# 85-2031red.net
KiCad netlist of a schematic drawn in EAGLE
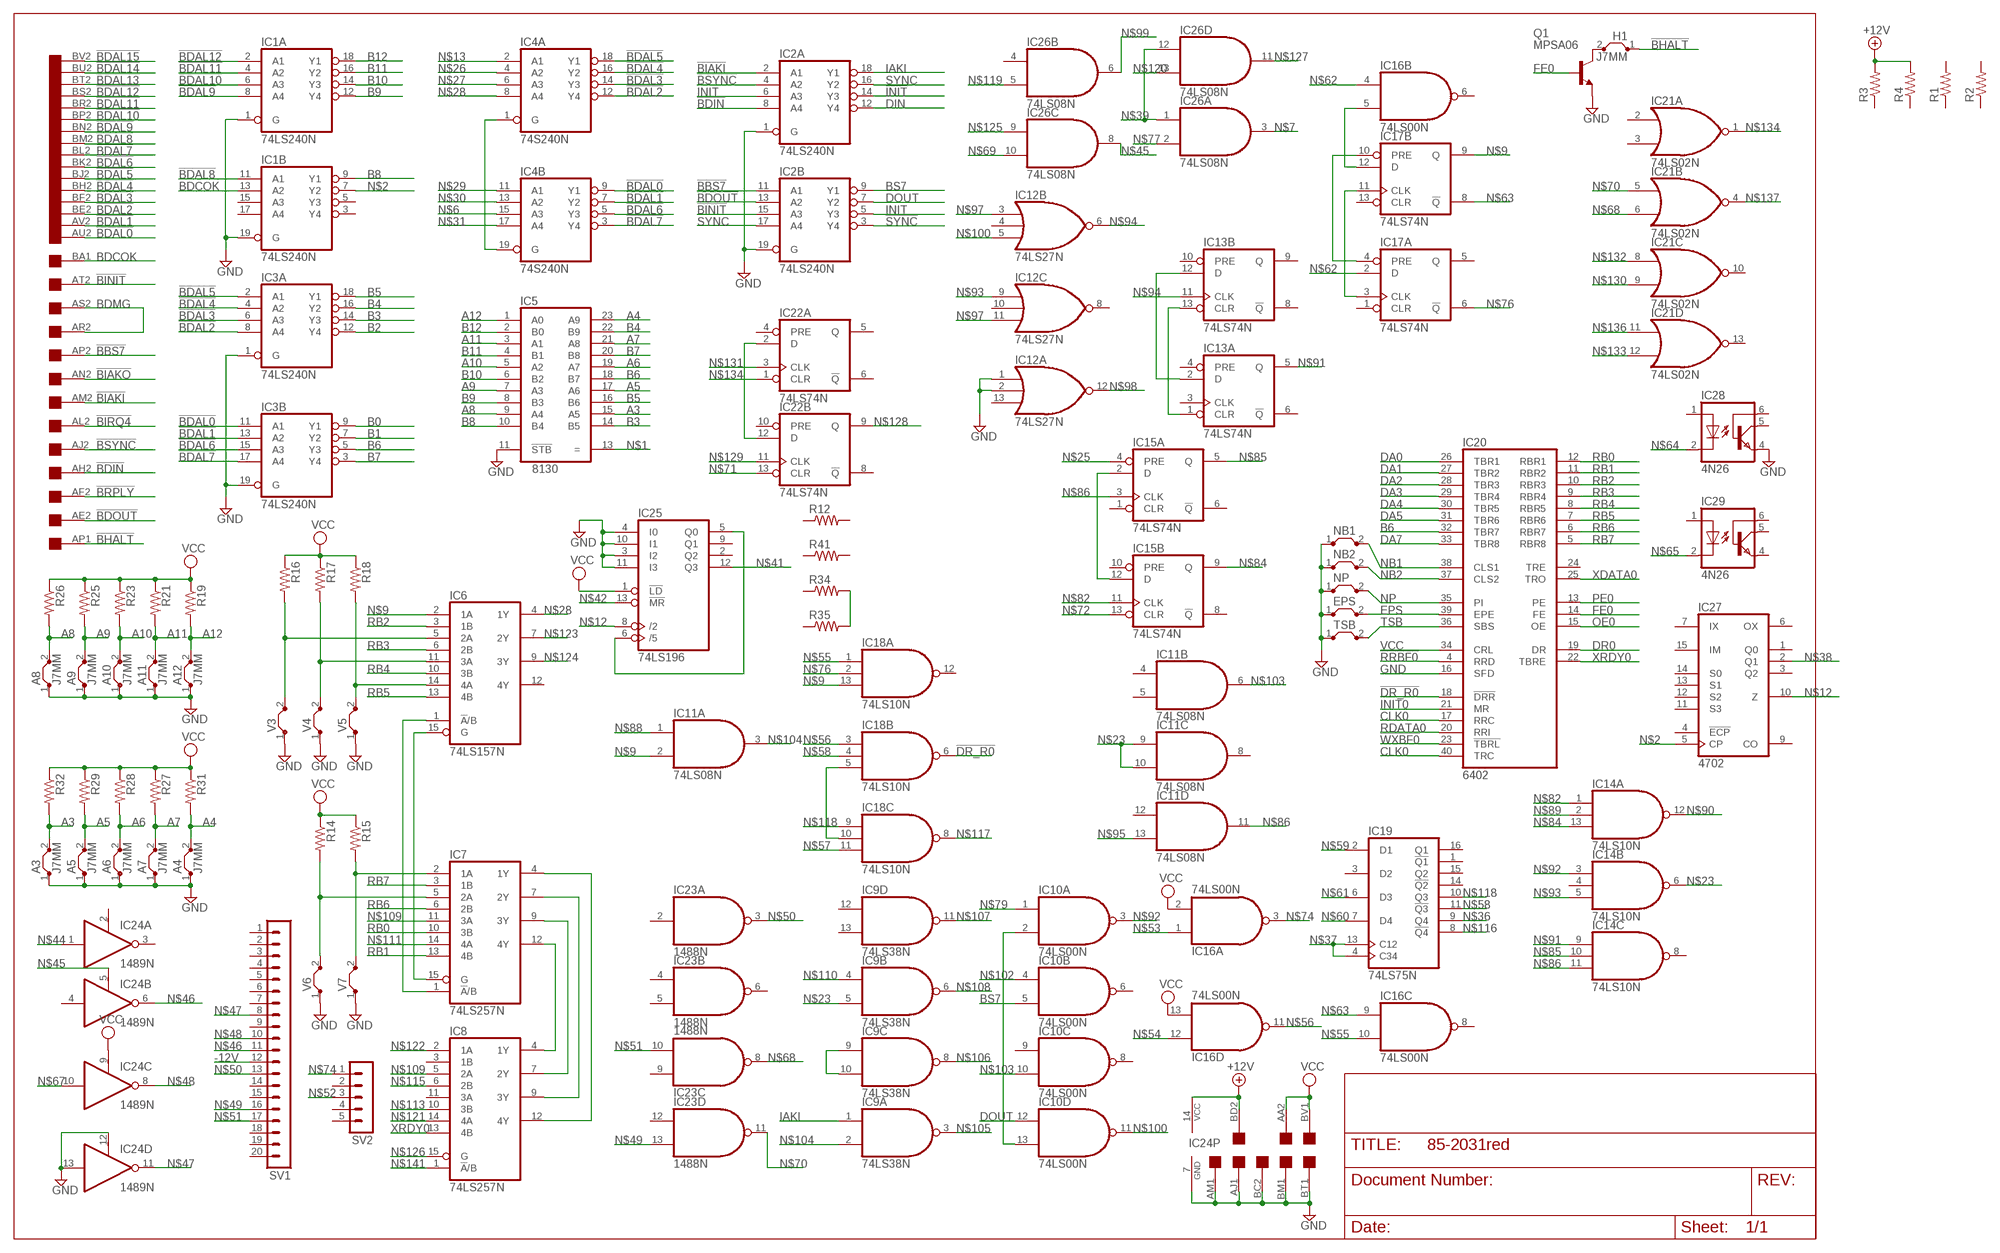
[diagram p0: schematic, sheet 1]

(export (version "E")
  (design (tool "Eeschema 10.0.6"))
  (components
    (comp (ref "A3")
      (value "J7MM")
      (footprint "eagle-import:07")
      (libsource (lib "eagle-import") (part "J7MM"))
    )
    (comp (ref "A4")
      (value "J7MM")
      (footprint "eagle-import:07")
      (libsource (lib "eagle-import") (part "J7MM"))
    )
    (comp (ref "A5")
      (value "J7MM")
      (footprint "eagle-import:07")
      (libsource (lib "eagle-import") (part "J7MM"))
    )
    (comp (ref "A6")
      (value "J7MM")
      (footprint "eagle-import:07")
      (libsource (lib "eagle-import") (part "J7MM"))
    )
    (comp (ref "A7")
      (value "J7MM")
      (footprint "eagle-import:07")
      (libsource (lib "eagle-import") (part "J7MM"))
    )
    (comp (ref "A8")
      (value "J7MM")
      (footprint "eagle-import:07")
      (libsource (lib "eagle-import") (part "J7MM"))
    )
    (comp (ref "A9")
      (value "J7MM")
      (footprint "eagle-import:07")
      (libsource (lib "eagle-import") (part "J7MM"))
    )
    (comp (ref "A10")
      (value "J7MM")
      (footprint "eagle-import:07")
      (libsource (lib "eagle-import") (part "J7MM"))
    )
    (comp (ref "A11")
      (value "J7MM")
      (footprint "eagle-import:07")
      (libsource (lib "eagle-import") (part "J7MM"))
    )
    (comp (ref "A12")
      (value "J7MM")
      (footprint "eagle-import:07")
      (libsource (lib "eagle-import") (part "J7MM"))
    )
    (comp (ref "EDGE$")
      (value "DOUBLE")
      (footprint "eagle-import:EDGE-CON4")
      (libsource (lib "eagle-import") (part "DOUBLE"))
    )
    (comp (ref "EPS")
      (value "J7MM")
      (footprint "eagle-import:07")
      (libsource (lib "eagle-import") (part "J7MM"))
    )
    (comp (ref "H1")
      (value "J7MM")
      (footprint "eagle-import:07")
      (libsource (lib "eagle-import") (part "J7MM"))
    )
    (comp (ref "IC1")
      (value "74LS240N")
      (footprint "eagle-import:DIL20")
      (libsource (lib "eagle-import") (part "74240NLS"))
    )
    (comp (ref "IC2")
      (value "74LS240N")
      (footprint "eagle-import:DIL20")
      (libsource (lib "eagle-import") (part "74240NLS"))
    )
    (comp (ref "IC3")
      (value "74LS240N")
      (footprint "eagle-import:DIL20")
      (libsource (lib "eagle-import") (part "74240NLS"))
    )
    (comp (ref "IC4")
      (value "74S240N")
      (footprint "eagle-import:DIL20")
      (libsource (lib "eagle-import") (part "74240NS"))
    )
    (comp (ref "IC5")
      (value "8130")
      (footprint "eagle-import:DIL24")
      (libsource (lib "eagle-import") (part "8130"))
    )
    (comp (ref "IC6")
      (value "74LS157N")
      (footprint "eagle-import:DIL16")
      (libsource (lib "eagle-import") (part "74157NLS"))
    )
    (comp (ref "IC7")
      (value "74LS257N")
      (footprint "eagle-import:DIL16")
      (libsource (lib "eagle-import") (part "74257NLS"))
    )
    (comp (ref "IC8")
      (value "74LS257N")
      (footprint "eagle-import:DIL16")
      (libsource (lib "eagle-import") (part "74257NLS"))
    )
    (comp (ref "IC9")
      (value "74LS38N")
      (footprint "eagle-import:DIL14")
      (libsource (lib "eagle-import") (part "7438NLS"))
    )
    (comp (ref "IC10")
      (value "74LS00N")
      (footprint "eagle-import:DIL14")
      (libsource (lib "eagle-import") (part "7400NLS"))
    )
    (comp (ref "IC11")
      (value "74LS08N")
      (footprint "eagle-import:DIL14")
      (libsource (lib "eagle-import") (part "7408NLS"))
    )
    (comp (ref "IC12")
      (value "74LS27N")
      (footprint "eagle-import:DIL14")
      (libsource (lib "eagle-import") (part "7427NLS"))
    )
    (comp (ref "IC13")
      (value "74LS74N")
      (footprint "eagle-import:DIL14")
      (libsource (lib "eagle-import") (part "7474NLS"))
    )
    (comp (ref "IC14")
      (value "74LS10N")
      (footprint "eagle-import:DIL14")
      (libsource (lib "eagle-import") (part "7410NLS"))
    )
    (comp (ref "IC15")
      (value "74LS74N")
      (footprint "eagle-import:DIL14")
      (libsource (lib "eagle-import") (part "7474NLS"))
    )
    (comp (ref "IC16")
      (value "74LS00N")
      (footprint "eagle-import:DIL14")
      (libsource (lib "eagle-import") (part "7400NLS"))
    )
    (comp (ref "IC17")
      (value "74LS74N")
      (footprint "eagle-import:DIL14")
      (libsource (lib "eagle-import") (part "7474NLS"))
    )
    (comp (ref "IC18")
      (value "74LS10N")
      (footprint "eagle-import:DIL14")
      (libsource (lib "eagle-import") (part "7410NLS"))
    )
    (comp (ref "IC19")
      (value "74LS75N")
      (footprint "eagle-import:DIL16")
      (libsource (lib "eagle-import") (part "7475NLS"))
    )
    (comp (ref "IC20")
      (value "6402")
      (footprint "eagle-import:DIL40")
      (libsource (lib "eagle-import") (part "HD6402"))
    )
    (comp (ref "IC21")
      (value "74LS02N")
      (footprint "eagle-import:DIL14")
      (libsource (lib "eagle-import") (part "7402NLS"))
    )
    (comp (ref "IC22")
      (value "74LS74N")
      (footprint "eagle-import:DIL14")
      (libsource (lib "eagle-import") (part "7474NLS"))
    )
    (comp (ref "IC23")
      (value "1488N")
      (footprint "eagle-import:DIL14")
      (libsource (lib "eagle-import") (part "1488N"))
    )
    (comp (ref "IC24")
      (value "1489N")
      (footprint "eagle-import:DIL14")
      (libsource (lib "eagle-import") (part "1489N"))
    )
    (comp (ref "IC25")
      (value "74LS196")
      (footprint "eagle-import:DIL14")
      (libsource (lib "eagle-import") (part "74LS196"))
    )
    (comp (ref "IC26")
      (value "74LS08N")
      (footprint "eagle-import:DIL14")
      (libsource (lib "eagle-import") (part "7408NLS"))
    )
    (comp (ref "IC27")
      (value "4702")
      (footprint "eagle-import:DIL16")
      (libsource (lib "eagle-import") (part "HD4702"))
    )
    (comp (ref "IC28")
      (value "4N26")
      (footprint "eagle-import:DIL06")
      (fields (field (name "MF") "FAIRCHILD SEMICONDUCTOR") (field (name "MPN") "4N35"))
      (libsource (lib "eagle-import") (part "4N35"))
    )
    (comp (ref "IC29")
      (value "4N26")
      (footprint "eagle-import:DIL06")
      (fields (field (name "MF") "FAIRCHILD SEMICONDUCTOR") (field (name "MPN") "4N35"))
      (libsource (lib "eagle-import") (part "4N35"))
    )
    (comp (ref "NB1")
      (value "J7MM")
      (footprint "eagle-import:07")
      (libsource (lib "eagle-import") (part "J7MM"))
    )
    (comp (ref "NB2")
      (value "J7MM")
      (footprint "eagle-import:07")
      (libsource (lib "eagle-import") (part "J7MM"))
    )
    (comp (ref "NP")
      (value "J7MM")
      (footprint "eagle-import:07")
      (libsource (lib "eagle-import") (part "J7MM"))
    )
    (comp (ref "Q1")
      (value "MPSA06")
      (footprint "eagle-import:TO92L")
      (libsource (lib "eagle-import") (part "-NPN-TO92L"))
    )
    (comp (ref "R1")
      (value "R-US_0207/10")
      (footprint "eagle-import:0207_10")
      (libsource (lib "eagle-import") (part "R-US_0207/10"))
    )
    (comp (ref "R2")
      (value "R-US_0207/10")
      (footprint "eagle-import:0207_10")
      (libsource (lib "eagle-import") (part "R-US_0207/10"))
    )
    (comp (ref "R3")
      (value "R-US_0207/10")
      (footprint "eagle-import:0207_10")
      (libsource (lib "eagle-import") (part "R-US_0207/10"))
    )
    (comp (ref "R4")
      (value "R-US_0207/10")
      (footprint "eagle-import:0207_10")
      (libsource (lib "eagle-import") (part "R-US_0207/10"))
    )
    (comp (ref "R12")
      (value "R-US_0207/10")
      (footprint "eagle-import:0207_10")
      (libsource (lib "eagle-import") (part "R-US_0207/10"))
    )
    (comp (ref "R14")
      (value "R-US_0207/10")
      (footprint "eagle-import:0207_10")
      (libsource (lib "eagle-import") (part "R-US_0207/10"))
    )
    (comp (ref "R15")
      (value "R-US_0207/10")
      (footprint "eagle-import:0207_10")
      (libsource (lib "eagle-import") (part "R-US_0207/10"))
    )
    (comp (ref "R16")
      (value "R-US_0207/10")
      (footprint "eagle-import:0207_10")
      (libsource (lib "eagle-import") (part "R-US_0207/10"))
    )
    (comp (ref "R17")
      (value "R-US_0207/10")
      (footprint "eagle-import:0207_10")
      (libsource (lib "eagle-import") (part "R-US_0207/10"))
    )
    (comp (ref "R18")
      (value "R-US_0207/10")
      (footprint "eagle-import:0207_10")
      (libsource (lib "eagle-import") (part "R-US_0207/10"))
    )
    (comp (ref "R19")
      (value "R-US_0207/10")
      (footprint "eagle-import:0207_10")
      (libsource (lib "eagle-import") (part "R-US_0207/10"))
    )
    (comp (ref "R21")
      (value "R-US_0207/10")
      (footprint "eagle-import:0207_10")
      (libsource (lib "eagle-import") (part "R-US_0207/10"))
    )
    (comp (ref "R23")
      (value "R-US_0207/10")
      (footprint "eagle-import:0207_10")
      (libsource (lib "eagle-import") (part "R-US_0207/10"))
    )
    (comp (ref "R25")
      (value "R-US_0207/10")
      (footprint "eagle-import:0207_10")
      (libsource (lib "eagle-import") (part "R-US_0207/10"))
    )
    (comp (ref "R26")
      (value "R-US_0207/10")
      (footprint "eagle-import:0207_10")
      (libsource (lib "eagle-import") (part "R-US_0207/10"))
    )
    (comp (ref "R27")
      (value "R-US_0207/10")
      (footprint "eagle-import:0207_10")
      (libsource (lib "eagle-import") (part "R-US_0207/10"))
    )
    (comp (ref "R28")
      (value "R-US_0207/10")
      (footprint "eagle-import:0207_10")
      (libsource (lib "eagle-import") (part "R-US_0207/10"))
    )
    (comp (ref "R29")
      (value "R-US_0207/10")
      (footprint "eagle-import:0207_10")
      (libsource (lib "eagle-import") (part "R-US_0207/10"))
    )
    (comp (ref "R31")
      (value "R-US_0207/10")
      (footprint "eagle-import:0207_10")
      (libsource (lib "eagle-import") (part "R-US_0207/10"))
    )
    (comp (ref "R32")
      (value "R-US_0207/10")
      (footprint "eagle-import:0207_10")
      (libsource (lib "eagle-import") (part "R-US_0207/10"))
    )
    (comp (ref "R34")
      (value "R-US_0207/10")
      (footprint "eagle-import:0207_10")
      (libsource (lib "eagle-import") (part "R-US_0207/10"))
    )
    (comp (ref "R35")
      (value "R-US_0207/10")
      (footprint "eagle-import:0207_10")
      (libsource (lib "eagle-import") (part "R-US_0207/10"))
    )
    (comp (ref "R41")
      (value "R-US_0207/10")
      (footprint "eagle-import:0207_10")
      (libsource (lib "eagle-import") (part "R-US_0207/10"))
    )
    (comp (ref "SV1")
      (value "MA20-1")
      (footprint "eagle-import:MA20-1")
      (libsource (lib "eagle-import") (part "MA20-1"))
    )
    (comp (ref "SV2")
      (value "MA05-1")
      (footprint "eagle-import:MA05-1")
      (libsource (lib "eagle-import") (part "MA05-1"))
    )
    (comp (ref "TSB")
      (value "J7MM")
      (footprint "eagle-import:07")
      (libsource (lib "eagle-import") (part "J7MM"))
    )
    (comp (ref "V3")
      (value "J7MM")
      (footprint "eagle-import:07")
      (libsource (lib "eagle-import") (part "J7MM"))
    )
    (comp (ref "V4")
      (value "J7MM")
      (footprint "eagle-import:07")
      (libsource (lib "eagle-import") (part "J7MM"))
    )
    (comp (ref "V5")
      (value "J7MM")
      (footprint "eagle-import:07")
      (libsource (lib "eagle-import") (part "J7MM"))
    )
    (comp (ref "V6")
      (value "J7MM")
      (footprint "eagle-import:07")
      (libsource (lib "eagle-import") (part "J7MM"))
    )
    (comp (ref "V7")
      (value "J7MM")
      (footprint "eagle-import:07")
      (libsource (lib "eagle-import") (part "J7MM"))
    )
  )
  (nets
    (net (code "1") (name "+12V") (class "Default")
      (node (ref "EDGE$") (pin "BD2") (pinfunction "1_BD2") (pintype "bidirectional"))
      (node (ref "IC24") (pin "14") (pinfunction "VCC_14") (pintype "power_in"))
      (node (ref "R3") (pin "2") (pinfunction "2_2") (pintype "passive"))
      (node (ref "R4") (pin "2") (pinfunction "2_2") (pintype "passive"))
    )
    (net (code "2") (name "/-12V") (class "Default")
      (node (ref "SV1") (pin "12") (pinfunction "12_12") (pintype "passive"))
    )
    (net (code "3") (name "/A3") (class "Default")
      (node (ref "A3") (pin "2") (pinfunction "2_2") (pintype "passive"))
      (node (ref "IC5") (pin "15") (pinfunction "A5_15") (pintype "input"))
      (node (ref "R32") (pin "2") (pinfunction "2_2") (pintype "passive"))
    )
    (net (code "4") (name "/A4") (class "Default")
      (node (ref "A4") (pin "2") (pinfunction "2_2") (pintype "passive"))
      (node (ref "IC5") (pin "23") (pinfunction "A9_23") (pintype "input"))
      (node (ref "R31") (pin "2") (pinfunction "2_2") (pintype "passive"))
    )
    (net (code "5") (name "/A5") (class "Default")
      (node (ref "A5") (pin "2") (pinfunction "2_2") (pintype "passive"))
      (node (ref "IC5") (pin "17") (pinfunction "A6_17") (pintype "input"))
      (node (ref "R29") (pin "2") (pinfunction "2_2") (pintype "passive"))
    )
    (net (code "6") (name "/A6") (class "Default")
      (node (ref "A6") (pin "2") (pinfunction "2_2") (pintype "passive"))
      (node (ref "IC5") (pin "19") (pinfunction "A7_19") (pintype "input"))
      (node (ref "R28") (pin "2") (pinfunction "2_2") (pintype "passive"))
    )
    (net (code "7") (name "/A7") (class "Default")
      (node (ref "A7") (pin "2") (pinfunction "2_2") (pintype "passive"))
      (node (ref "IC5") (pin "21") (pinfunction "A8_21") (pintype "input"))
      (node (ref "R27") (pin "2") (pinfunction "2_2") (pintype "passive"))
    )
    (net (code "8") (name "/A8") (class "Default")
      (node (ref "A8") (pin "2") (pinfunction "2_2") (pintype "passive"))
      (node (ref "IC5") (pin "9") (pinfunction "A4_9") (pintype "input"))
      (node (ref "R26") (pin "2") (pinfunction "2_2") (pintype "passive"))
    )
    (net (code "9") (name "/A9") (class "Default")
      (node (ref "A9") (pin "2") (pinfunction "2_2") (pintype "passive"))
      (node (ref "IC5") (pin "7") (pinfunction "A3_7") (pintype "input"))
      (node (ref "R25") (pin "2") (pinfunction "2_2") (pintype "passive"))
    )
    (net (code "10") (name "/A10") (class "Default")
      (node (ref "A10") (pin "2") (pinfunction "2_2") (pintype "passive"))
      (node (ref "IC5") (pin "5") (pinfunction "A2_5") (pintype "input"))
      (node (ref "R23") (pin "2") (pinfunction "2_2") (pintype "passive"))
    )
    (net (code "11") (name "/A11") (class "Default")
      (node (ref "A11") (pin "2") (pinfunction "2_2") (pintype "passive"))
      (node (ref "IC5") (pin "3") (pinfunction "A1_3") (pintype "input"))
      (node (ref "R21") (pin "2") (pinfunction "2_2") (pintype "passive"))
    )
    (net (code "12") (name "/A12") (class "Default")
      (node (ref "A12") (pin "2") (pinfunction "2_2") (pintype "passive"))
      (node (ref "IC5") (pin "1") (pinfunction "A0_1") (pintype "input"))
      (node (ref "R19") (pin "2") (pinfunction "2_2") (pintype "passive"))
    )
    (net (code "13") (name "/B0") (class "Default")
      (node (ref "IC22") (pin "12") (pinfunction "D_12") (pintype "input"))
      (node (ref "IC22") (pin "2") (pinfunction "D_2") (pintype "input"))
      (node (ref "IC3") (pin "9") (pinfunction "Y1_9") (pintype "tri_state"))
    )
    (net (code "14") (name "/B1") (class "Default")
      (node (ref "IC3") (pin "7") (pinfunction "Y2_7") (pintype "tri_state"))
    )
    (net (code "15") (name "/B2") (class "Default")
      (node (ref "IC3") (pin "12") (pinfunction "Y4_12") (pintype "tri_state"))
    )
    (net (code "16") (name "/B3") (class "Default")
      (node (ref "IC3") (pin "14") (pinfunction "Y3_14") (pintype "tri_state"))
      (node (ref "IC5") (pin "14") (pinfunction "B5_14") (pintype "input"))
    )
    (net (code "17") (name "/B4") (class "Default")
      (node (ref "IC3") (pin "16") (pinfunction "Y2_16") (pintype "tri_state"))
      (node (ref "IC5") (pin "22") (pinfunction "B9_22") (pintype "input"))
    )
    (net (code "18") (name "/B5") (class "Default")
      (node (ref "IC3") (pin "18") (pinfunction "Y1_18") (pintype "tri_state"))
      (node (ref "IC5") (pin "16") (pinfunction "B6_16") (pintype "input"))
    )
    (net (code "19") (name "/B6") (class "Default")
      (node (ref "IC20") (pin "32") (pinfunction "TBR7_32") (pintype "input"))
      (node (ref "IC3") (pin "5") (pinfunction "Y3_5") (pintype "tri_state"))
      (node (ref "IC5") (pin "18") (pinfunction "B7_18") (pintype "input"))
    )
    (net (code "20") (name "/B7") (class "Default")
      (node (ref "IC3") (pin "3") (pinfunction "Y4_3") (pintype "tri_state"))
      (node (ref "IC5") (pin "20") (pinfunction "B8_20") (pintype "input"))
    )
    (net (code "21") (name "/B8") (class "Default")
      (node (ref "IC1") (pin "9") (pinfunction "Y1_9") (pintype "tri_state"))
      (node (ref "IC5") (pin "10") (pinfunction "B4_10") (pintype "input"))
    )
    (net (code "22") (name "/B9") (class "Default")
      (node (ref "IC1") (pin "12") (pinfunction "Y4_12") (pintype "tri_state"))
      (node (ref "IC5") (pin "8") (pinfunction "B3_8") (pintype "input"))
    )
    (net (code "23") (name "/B10") (class "Default")
      (node (ref "IC1") (pin "14") (pinfunction "Y3_14") (pintype "tri_state"))
      (node (ref "IC5") (pin "6") (pinfunction "B2_6") (pintype "input"))
    )
    (net (code "24") (name "/B11") (class "Default")
      (node (ref "IC1") (pin "16") (pinfunction "Y2_16") (pintype "tri_state"))
      (node (ref "IC5") (pin "4") (pinfunction "B1_4") (pintype "input"))
    )
    (net (code "25") (name "/B12") (class "Default")
      (node (ref "IC1") (pin "18") (pinfunction "Y1_18") (pintype "tri_state"))
      (node (ref "IC5") (pin "2") (pinfunction "B0_2") (pintype "input"))
    )
    (net (code "26") (name "/BDCOK") (class "Default")
      (node (ref "EDGE$") (pin "BA1") (pinfunction "1_BA1") (pintype "bidirectional"))
      (node (ref "IC1") (pin "13") (pinfunction "A2_13") (pintype "input"))
    )
    (net (code "27") (name "/BDMG") (class "Default")
      (node (ref "EDGE$") (pin "AR2") (pinfunction "1_AR2") (pintype "bidirectional"))
      (node (ref "EDGE$") (pin "AS2") (pinfunction "1_AS2") (pintype "bidirectional"))
    )
    (net (code "28") (name "/BS7") (class "Default")
      (node (ref "IC10") (pin "5") (pinfunction "I1_5") (pintype "input"))
      (node (ref "IC2") (pin "9") (pinfunction "Y1_9") (pintype "tri_state"))
    )
    (net (code "29") (name "/CLK0") (class "Default")
      (node (ref "IC20") (pin "17") (pinfunction "RRC_17") (pintype "input"))
      (node (ref "IC20") (pin "40") (pinfunction "TRC_40") (pintype "input"))
    )
    (net (code "30") (name "/DA0") (class "Default")
      (node (ref "IC20") (pin "26") (pinfunction "TBR1_26") (pintype "input"))
    )
    (net (code "31") (name "/DA1") (class "Default")
      (node (ref "IC20") (pin "27") (pinfunction "TBR2_27") (pintype "input"))
    )
    (net (code "32") (name "/DA2") (class "Default")
      (node (ref "IC20") (pin "28") (pinfunction "TBR3_28") (pintype "input"))
    )
    (net (code "33") (name "/DA3") (class "Default")
      (node (ref "IC20") (pin "29") (pinfunction "TBR4_29") (pintype "input"))
    )
    (net (code "34") (name "/DA4") (class "Default")
      (node (ref "IC20") (pin "30") (pinfunction "TBR5_30") (pintype "input"))
    )
    (net (code "35") (name "/DA5") (class "Default")
      (node (ref "IC20") (pin "31") (pinfunction "TBR6_31") (pintype "input"))
    )
    (net (code "36") (name "/DA7") (class "Default")
      (node (ref "IC20") (pin "33") (pinfunction "TBR8_33") (pintype "input"))
    )
    (net (code "37") (name "/DIN") (class "Default")
      (node (ref "IC2") (pin "12") (pinfunction "Y4_12") (pintype "tri_state"))
    )
    (net (code "38") (name "/DOUT") (class "Default")
      (node (ref "IC10") (pin "12") (pinfunction "I0_12") (pintype "input"))
      (node (ref "IC2") (pin "7") (pinfunction "Y2_7") (pintype "tri_state"))
    )
    (net (code "39") (name "/DR0") (class "Default")
      (node (ref "IC20") (pin "19") (pinfunction "DR_19") (pintype "tri_state"))
    )
    (net (code "40") (name "/EPS") (class "Default")
      (node (ref "EPS") (pin "2") (pinfunction "2_2") (pintype "passive"))
      (node (ref "IC20") (pin "39") (pinfunction "EPE_39") (pintype "input"))
    )
    (net (code "41") (name "/FE0") (class "Default")
      (node (ref "IC20") (pin "14") (pinfunction "FE_14") (pintype "tri_state"))
      (node (ref "Q1") (pin "2") (pinfunction "B_2") (pintype "passive"))
    )
    (net (code "42") (name "/IAKI") (class "Default")
      (node (ref "IC2") (pin "18") (pinfunction "Y1_18") (pintype "tri_state"))
      (node (ref "IC9") (pin "1") (pinfunction "I0_1") (pintype "input"))
    )
    (net (code "43") (name "/INIT") (class "Default")
      (node (ref "IC2") (pin "5") (pinfunction "Y3_5") (pintype "tri_state"))
      (node (ref "IC2") (pin "6") (pinfunction "A3_6") (pintype "input"))
    )
    (net (code "44") (name "/INIT0") (class "Default")
      (node (ref "IC20") (pin "21") (pinfunction "MR_21") (pintype "input"))
    )
    (net (code "45") (name "/N$1") (class "Default")
      (node (ref "IC5") (pin "13") (pinfunction "=_13") (pintype "output"))
    )
    (net (code "46") (name "/N$2") (class "Default")
      (node (ref "IC1") (pin "7") (pinfunction "Y2_7") (pintype "tri_state"))
      (node (ref "IC27") (pin "5") (pinfunction "CP_5") (pintype "input"))
    )
    (net (code "47") (name "/N$6") (class "Default")
      (node (ref "IC4") (pin "15") (pinfunction "A3_15") (pintype "input"))
    )
    (net (code "48") (name "/N$7") (class "Default")
      (node (ref "IC26") (pin "3") (pinfunction "O_3") (pintype "output"))
      (node (ref "IC4") (pin "1") (pinfunction "G_1") (pintype "input"))
      (node (ref "IC4") (pin "19") (pinfunction "G_19") (pintype "input"))
    )
    (net (code "49") (name "/N$9") (class "Default")
      (node (ref "IC11") (pin "2") (pinfunction "I1_2") (pintype "input"))
      (node (ref "IC17") (pin "9") (pinfunction "Q_9") (pintype "output"))
      (node (ref "IC18") (pin "13") (pinfunction "I2_13") (pintype "input"))
      (node (ref "IC6") (pin "2") (pinfunction "1A_2") (pintype "input"))
    )
    (net (code "50") (name "/N$12") (class "Default")
      (node (ref "IC25") (pin "8") (pinfunction "/2_8") (pintype "bidirectional"))
      (node (ref "IC27") (pin "10") (pinfunction "Z_10") (pintype "output"))
    )
    (net (code "51") (name "/N$13") (class "Default")
      (node (ref "IC4") (pin "2") (pinfunction "A1_2") (pintype "input"))
    )
    (net (code "52") (name "/N$23") (class "Default")
      (node (ref "IC11") (pin "10") (pinfunction "I1_10") (pintype "input"))
      (node (ref "IC11") (pin "9") (pinfunction "I0_9") (pintype "input"))
      (node (ref "IC14") (pin "6") (pinfunction "O_6") (pintype "output"))
      (node (ref "IC9") (pin "5") (pinfunction "I1_5") (pintype "input"))
    )
    (net (code "53") (name "/N$25") (class "Default")
      (node (ref "IC13") (pin "1") (pinfunction "CLR_1") (pintype "input"))
      (node (ref "IC13") (pin "13") (pinfunction "CLR_13") (pintype "input"))
      (node (ref "IC15") (pin "4") (pinfunction "PRE_4") (pintype "input"))
    )
    (net (code "54") (name "/N$26") (class "Default")
      (node (ref "IC4") (pin "4") (pinfunction "A2_4") (pintype "input"))
    )
    (net (code "55") (name "/N$27") (class "Default")
      (node (ref "IC4") (pin "6") (pinfunction "A3_6") (pintype "input"))
    )
    (net (code "56") (name "/N$28") (class "Default")
      (node (ref "IC4") (pin "8") (pinfunction "A4_8") (pintype "input"))
      (node (ref "IC6") (pin "4") (pinfunction "1Y_4") (pintype "output"))
    )
    (net (code "57") (name "/N$29") (class "Default")
      (node (ref "IC4") (pin "11") (pinfunction "A1_11") (pintype "input"))
    )
    (net (code "58") (name "/N$30") (class "Default")
      (node (ref "IC4") (pin "13") (pinfunction "A2_13") (pintype "input"))
    )
    (net (code "59") (name "/N$31") (class "Default")
      (node (ref "IC4") (pin "17") (pinfunction "A4_17") (pintype "input"))
    )
    (net (code "60") (name "/N$36") (class "Default")
      (node (ref "IC18") (pin "10") (pinfunction "I1_10") (pintype "input"))
      (node (ref "IC18") (pin "5") (pinfunction "I2_5") (pintype "input"))
      (node (ref "IC19") (pin "9") (pinfunction "Q4_9") (pintype "output"))
    )
    (net (code "61") (name "/N$37") (class "Default")
      (node (ref "IC19") (pin "13") (pinfunction "C12_13") (pintype "input"))
      (node (ref "IC19") (pin "4") (pinfunction "C34_4") (pintype "input"))
    )
    (net (code "62") (name "/N$38") (class "Default")
      (node (ref "IC27") (pin "2") (pinfunction "Q1_2") (pintype "output"))
    )
    (net (code "63") (name "/N$39") (class "Default")
      (node (ref "IC26") (pin "1") (pinfunction "I0_1") (pintype "input"))
      (node (ref "IC26") (pin "12") (pinfunction "I0_12") (pintype "input"))
    )
    (net (code "64") (name "/N$41") (class "Default")
      (node (ref "IC25") (pin "12") (pinfunction "Q3_12") (pintype "output"))
    )
    (net (code "65") (name "/N$42") (class "Default")
      (node (ref "IC25") (pin "13") (pinfunction "~{MR}_13") (pintype "input"))
    )
    (net (code "66") (name "/N$44") (class "Default")
      (node (ref "IC24") (pin "1") (pinfunction "I_1") (pintype "input"))
    )
    (net (code "67") (name "/N$45") (class "Default")
      (node (ref "IC24") (pin "5") (pinfunction "RC_5") (pintype "input"))
      (node (ref "IC26") (pin "8") (pinfunction "O_8") (pintype "output"))
    )
    (net (code "68") (name "/N$46") (class "Default")
      (node (ref "IC24") (pin "6") (pinfunction "O_6") (pintype "output"))
      (node (ref "SV1") (pin "11") (pinfunction "11_11") (pintype "passive"))
    )
    (net (code "69") (name "/N$47") (class "Default")
      (node (ref "IC24") (pin "11") (pinfunction "O_11") (pintype "output"))
      (node (ref "SV1") (pin "8") (pinfunction "8_8") (pintype "passive"))
    )
    (net (code "70") (name "/N$48") (class "Default")
      (node (ref "IC24") (pin "8") (pinfunction "O_8") (pintype "output"))
      (node (ref "SV1") (pin "10") (pinfunction "10_10") (pintype "passive"))
    )
    (net (code "71") (name "/N$49") (class "Default")
      (node (ref "IC23") (pin "13") (pinfunction "I1_13") (pintype "input"))
      (node (ref "SV1") (pin "16") (pinfunction "16_16") (pintype "passive"))
    )
    (net (code "72") (name "/N$50") (class "Default")
      (node (ref "IC23") (pin "3") (pinfunction "O_3") (pintype "output"))
      (node (ref "SV1") (pin "13") (pinfunction "13_13") (pintype "passive"))
    )
    (net (code "73") (name "/N$51") (class "Default")
      (node (ref "IC23") (pin "10") (pinfunction "I1_10") (pintype "input"))
      (node (ref "SV1") (pin "17") (pinfunction "17_17") (pintype "passive"))
    )
    (net (code "74") (name "/N$52") (class "Default")
      (node (ref "SV2") (pin "3") (pinfunction "3_3") (pintype "passive"))
    )
    (net (code "75") (name "/N$53") (class "Default")
      (node (ref "IC16") (pin "1") (pinfunction "I0_1") (pintype "input"))
    )
    (net (code "76") (name "/N$54") (class "Default")
      (node (ref "IC16") (pin "12") (pinfunction "I0_12") (pintype "input"))
    )
    (net (code "77") (name "/N$55") (class "Default")
      (node (ref "IC16") (pin "10") (pinfunction "I1_10") (pintype "input"))
      (node (ref "IC18") (pin "1") (pinfunction "I0_1") (pintype "input"))
    )
    (net (code "78") (name "/N$56") (class "Default")
      (node (ref "IC16") (pin "11") (pinfunction "O_11") (pintype "output"))
      (node (ref "IC18") (pin "3") (pinfunction "I0_3") (pintype "input"))
    )
    (net (code "79") (name "/N$57") (class "Default")
      (node (ref "IC18") (pin "11") (pinfunction "I2_11") (pintype "input"))
    )
    (net (code "80") (name "/N$58") (class "Default")
      (node (ref "IC18") (pin "4") (pinfunction "I1_4") (pintype "input"))
      (node (ref "IC19") (pin "11") (pinfunction "~{Q3}_11") (pintype "output"))
    )
    (net (code "81") (name "/N$59") (class "Default")
      (node (ref "IC19") (pin "2") (pinfunction "D1_2") (pintype "input"))
    )
    (net (code "82") (name "/N$60") (class "Default")
      (node (ref "IC19") (pin "7") (pinfunction "D4_7") (pintype "input"))
    )
    (net (code "83") (name "/N$61") (class "Default")
      (node (ref "IC19") (pin "6") (pinfunction "D3_6") (pintype "input"))
    )
    (net (code "84") (name "/N$62") (class "Default")
      (node (ref "IC16") (pin "4") (pinfunction "I0_4") (pintype "input"))
      (node (ref "IC17") (pin "2") (pinfunction "D_2") (pintype "input"))
    )
    (net (code "85") (name "/N$63") (class "Default")
      (node (ref "IC16") (pin "9") (pinfunction "I0_9") (pintype "input"))
      (node (ref "IC17") (pin "8") (pinfunction "~{Q}_8") (pintype "output"))
    )
    (net (code "86") (name "/N$64") (class "Default")
      (node (ref "IC28") (pin "2") (pinfunction "C_2") (pintype "passive"))
    )
    (net (code "87") (name "/N$65") (class "Default")
      (node (ref "IC29") (pin "2") (pinfunction "C_2") (pintype "passive"))
    )
    (net (code "88") (name "/N$67") (class "Default")
      (node (ref "IC24") (pin "10") (pinfunction "I_10") (pintype "input"))
    )
    (net (code "89") (name "/N$68") (class "Default")
      (node (ref "IC21") (pin "6") (pinfunction "I1_6") (pintype "input"))
      (node (ref "IC23") (pin "8") (pinfunction "O_8") (pintype "output"))
    )
    (net (code "90") (name "/N$69") (class "Default")
      (node (ref "IC26") (pin "10") (pinfunction "I1_10") (pintype "input"))
    )
    (net (code "91") (name "/N$70") (class "Default")
      (node (ref "IC21") (pin "5") (pinfunction "I0_5") (pintype "input"))
      (node (ref "IC23") (pin "11") (pinfunction "O_11") (pintype "output"))
    )
    (net (code "92") (name "/N$71") (class "Default")
      (node (ref "IC22") (pin "13") (pinfunction "CLR_13") (pintype "input"))
    )
    (net (code "93") (name "/N$72") (class "Default")
      (node (ref "IC15") (pin "13") (pinfunction "CLR_13") (pintype "input"))
    )
    (net (code "94") (name "/N$74") (class "Default")
      (node (ref "IC16") (pin "3") (pinfunction "O_3") (pintype "output"))
      (node (ref "SV2") (pin "1") (pinfunction "1_1") (pintype "passive"))
    )
    (net (code "95") (name "/N$76") (class "Default")
      (node (ref "IC17") (pin "6") (pinfunction "~{Q}_6") (pintype "output"))
      (node (ref "IC18") (pin "2") (pinfunction "I1_2") (pintype "input"))
    )
    (net (code "96") (name "/N$77") (class "Default")
      (node (ref "IC26") (pin "2") (pinfunction "I1_2") (pintype "input"))
    )
    (net (code "97") (name "/N$79") (class "Default")
      (node (ref "IC10") (pin "1") (pinfunction "I0_1") (pintype "input"))
    )
    (net (code "98") (name "/N$82") (class "Default")
      (node (ref "IC14") (pin "1") (pinfunction "I0_1") (pintype "input"))
      (node (ref "IC15") (pin "11") (pinfunction "CLK_11") (pintype "input"))
    )
    (net (code "99") (name "/N$84") (class "Default")
      (node (ref "IC14") (pin "13") (pinfunction "I2_13") (pintype "input"))
      (node (ref "IC15") (pin "9") (pinfunction "Q_9") (pintype "output"))
    )
    (net (code "100") (name "/N$85") (class "Default")
      (node (ref "IC14") (pin "10") (pinfunction "I1_10") (pintype "input"))
      (node (ref "IC15") (pin "5") (pinfunction "Q_5") (pintype "output"))
    )
    (net (code "101") (name "/N$86") (class "Default")
      (node (ref "IC11") (pin "11") (pinfunction "O_11") (pintype "output"))
      (node (ref "IC14") (pin "11") (pinfunction "I2_11") (pintype "input"))
      (node (ref "IC15") (pin "3") (pinfunction "CLK_3") (pintype "input"))
    )
    (net (code "102") (name "/N$88") (class "Default")
      (node (ref "IC11") (pin "1") (pinfunction "I0_1") (pintype "input"))
    )
    (net (code "103") (name "/N$89") (class "Default")
      (node (ref "IC14") (pin "2") (pinfunction "I1_2") (pintype "input"))
    )
    (net (code "104") (name "/N$90") (class "Default")
      (node (ref "IC14") (pin "12") (pinfunction "O_12") (pintype "output"))
    )
    (net (code "105") (name "/N$91") (class "Default")
      (node (ref "IC13") (pin "5") (pinfunction "Q_5") (pintype "output"))
      (node (ref "IC14") (pin "9") (pinfunction "I0_9") (pintype "input"))
    )
    (net (code "106") (name "/N$92") (class "Default")
      (node (ref "IC10") (pin "3") (pinfunction "O_3") (pintype "output"))
      (node (ref "IC14") (pin "3") (pinfunction "I0_3") (pintype "input"))
    )
    (net (code "107") (name "/N$93") (class "Default")
      (node (ref "IC12") (pin "9") (pinfunction "I0_9") (pintype "input"))
      (node (ref "IC14") (pin "5") (pinfunction "I2_5") (pintype "input"))
    )
    (net (code "108") (name "/N$94") (class "Default")
      (node (ref "IC12") (pin "6") (pinfunction "O_6") (pintype "output"))
      (node (ref "IC13") (pin "11") (pinfunction "CLK_11") (pintype "input"))
    )
    (net (code "109") (name "/N$95") (class "Default")
      (node (ref "IC11") (pin "13") (pinfunction "I1_13") (pintype "input"))
    )
    (net (code "110") (name "/N$97") (class "Default")
      (node (ref "IC12") (pin "11") (pinfunction "I2_11") (pintype "input"))
      (node (ref "IC12") (pin "3") (pinfunction "I0_3") (pintype "input"))
    )
    (net (code "111") (name "/N$98") (class "Default")
      (node (ref "IC12") (pin "12") (pinfunction "O_12") (pintype "output"))
    )
    (net (code "112") (name "/N$99") (class "Default")
      (node (ref "IC26") (pin "6") (pinfunction "O_6") (pintype "output"))
    )
    (net (code "113") (name "/N$100") (class "Default")
      (node (ref "IC10") (pin "11") (pinfunction "O_11") (pintype "output"))
      (node (ref "IC12") (pin "5") (pinfunction "I2_5") (pintype "input"))
    )
    (net (code "114") (name "/N$102") (class "Default")
      (node (ref "IC10") (pin "4") (pinfunction "I0_4") (pintype "input"))
    )
    (net (code "115") (name "/N$103") (class "Default")
      (node (ref "IC10") (pin "10") (pinfunction "I1_10") (pintype "input"))
      (node (ref "IC11") (pin "6") (pinfunction "O_6") (pintype "output"))
    )
    (net (code "116") (name "/N$104") (class "Default")
      (node (ref "IC11") (pin "3") (pinfunction "O_3") (pintype "output"))
      (node (ref "IC9") (pin "2") (pinfunction "I1_2") (pintype "input"))
    )
    (net (code "117") (name "/N$105") (class "Default")
      (node (ref "IC9") (pin "3") (pinfunction "O_3") (pintype "open_collector"))
    )
    (net (code "118") (name "/N$106") (class "Default")
      (node (ref "IC9") (pin "8") (pinfunction "O_8") (pintype "open_collector"))
    )
    (net (code "119") (name "/N$107") (class "Default")
      (node (ref "IC9") (pin "11") (pinfunction "O_11") (pintype "open_collector"))
    )
    (net (code "120") (name "/N$108") (class "Default")
      (node (ref "IC9") (pin "6") (pinfunction "O_6") (pintype "open_collector"))
    )
    (net (code "121") (name "/N$109") (class "Default")
      (node (ref "IC7") (pin "11") (pinfunction "3A_11") (pintype "input"))
      (node (ref "IC8") (pin "5") (pinfunction "2A_5") (pintype "input"))
    )
    (net (code "122") (name "/N$110") (class "Default")
      (node (ref "IC9") (pin "4") (pinfunction "I0_4") (pintype "input"))
    )
    (net (code "123") (name "/N$111") (class "Default")
      (node (ref "IC7") (pin "14") (pinfunction "4A_14") (pintype "input"))
    )
    (net (code "124") (name "/N$113") (class "Default")
      (node (ref "IC8") (pin "10") (pinfunction "3B_10") (pintype "input"))
    )
    (net (code "125") (name "/N$115") (class "Default")
      (node (ref "IC8") (pin "6") (pinfunction "2B_6") (pintype "input"))
    )
    (net (code "126") (name "/N$116") (class "Default")
      (node (ref "IC19") (pin "8") (pinfunction "~{Q4}_8") (pintype "output"))
    )
    (net (code "127") (name "/N$117") (class "Default")
      (node (ref "IC18") (pin "8") (pinfunction "O_8") (pintype "output"))
    )
    (net (code "128") (name "/N$118") (class "Default")
      (node (ref "IC18") (pin "9") (pinfunction "I0_9") (pintype "input"))
      (node (ref "IC19") (pin "10") (pinfunction "Q3_10") (pintype "output"))
    )
    (net (code "129") (name "/N$119") (class "Default")
      (node (ref "IC26") (pin "5") (pinfunction "I1_5") (pintype "input"))
    )
    (net (code "130") (name "/N$120") (class "Default")
      (node (ref "IC26") (pin "13") (pinfunction "I1_13") (pintype "input"))
    )
    (net (code "131") (name "/N$121") (class "Default")
      (node (ref "IC8") (pin "14") (pinfunction "4A_14") (pintype "input"))
    )
    (net (code "132") (name "/N$122") (class "Default")
      (node (ref "IC8") (pin "2") (pinfunction "1A_2") (pintype "input"))
    )
    (net (code "133") (name "/N$123") (class "Default")
      (node (ref "IC6") (pin "7") (pinfunction "2Y_7") (pintype "output"))
    )
    (net (code "134") (name "/N$124") (class "Default")
      (node (ref "IC6") (pin "9") (pinfunction "3Y_9") (pintype "output"))
    )
    (net (code "135") (name "/N$125") (class "Default")
      (node (ref "IC26") (pin "9") (pinfunction "I0_9") (pintype "input"))
    )
    (net (code "136") (name "/N$126") (class "Default")
      (node (ref "IC8") (pin "15") (pinfunction "G_15") (pintype "input"))
    )
    (net (code "137") (name "/N$127") (class "Default")
      (node (ref "IC26") (pin "11") (pinfunction "O_11") (pintype "output"))
    )
    (net (code "138") (name "/N$128") (class "Default")
      (node (ref "IC22") (pin "9") (pinfunction "Q_9") (pintype "output"))
    )
    (net (code "139") (name "/N$129") (class "Default")
      (node (ref "IC22") (pin "11") (pinfunction "CLK_11") (pintype "input"))
    )
    (net (code "140") (name "/N$130") (class "Default")
      (node (ref "IC21") (pin "9") (pinfunction "I1_9") (pintype "input"))
    )
    (net (code "141") (name "/N$131") (class "Default")
      (node (ref "IC22") (pin "3") (pinfunction "CLK_3") (pintype "input"))
    )
    (net (code "142") (name "/N$132") (class "Default")
      (node (ref "IC21") (pin "8") (pinfunction "I0_8") (pintype "input"))
    )
    (net (code "143") (name "/N$133") (class "Default")
      (node (ref "IC21") (pin "12") (pinfunction "I1_12") (pintype "input"))
    )
    (net (code "144") (name "/N$134") (class "Default")
      (node (ref "IC21") (pin "1") (pinfunction "O_1") (pintype "output"))
      (node (ref "IC22") (pin "1") (pinfunction "CLR_1") (pintype "input"))
    )
    (net (code "145") (name "/N$136") (class "Default")
      (node (ref "IC21") (pin "11") (pinfunction "I0_11") (pintype "input"))
    )
    (net (code "146") (name "/N$137") (class "Default")
      (node (ref "IC21") (pin "4") (pinfunction "O_4") (pintype "output"))
    )
    (net (code "147") (name "/N$141") (class "Default")
      (node (ref "IC8") (pin "1") (pinfunction "~{A}/B_1") (pintype "input"))
    )
    (net (code "148") (name "/NB1") (class "Default")
      (node (ref "IC20") (pin "38") (pinfunction "CLS1_38") (pintype "input"))
      (node (ref "NB1") (pin "2") (pinfunction "2_2") (pintype "passive"))
    )
    (net (code "149") (name "/NB2") (class "Default")
      (node (ref "IC20") (pin "37") (pinfunction "CLS2_37") (pintype "input"))
      (node (ref "NB2") (pin "2") (pinfunction "2_2") (pintype "passive"))
    )
    (net (code "150") (name "/NP") (class "Default")
      (node (ref "IC20") (pin "35") (pinfunction "PI_35") (pintype "input"))
      (node (ref "NP") (pin "2") (pinfunction "2_2") (pintype "passive"))
    )
    (net (code "151") (name "/OE0") (class "Default")
      (node (ref "IC20") (pin "15") (pinfunction "OE_15") (pintype "tri_state"))
    )
    (net (code "152") (name "/PE0") (class "Default")
      (node (ref "IC20") (pin "13") (pinfunction "PE_13") (pintype "tri_state"))
    )
    (net (code "153") (name "/RB0") (class "Default")
      (node (ref "IC20") (pin "12") (pinfunction "RBR1_12") (pintype "tri_state"))
      (node (ref "IC7") (pin "10") (pinfunction "3B_10") (pintype "input"))
    )
    (net (code "154") (name "/RB1") (class "Default")
      (node (ref "IC20") (pin "11") (pinfunction "RBR2_11") (pintype "tri_state"))
      (node (ref "IC7") (pin "13") (pinfunction "4B_13") (pintype "input"))
    )
    (net (code "155") (name "/RB2") (class "Default")
      (node (ref "IC20") (pin "10") (pinfunction "RBR3_10") (pintype "tri_state"))
      (node (ref "IC6") (pin "3") (pinfunction "1B_3") (pintype "input"))
    )
    (net (code "156") (name "/RB3") (class "Default")
      (node (ref "IC20") (pin "9") (pinfunction "RBR4_9") (pintype "tri_state"))
      (node (ref "IC6") (pin "6") (pinfunction "2B_6") (pintype "input"))
    )
    (net (code "157") (name "/RB4") (class "Default")
      (node (ref "IC20") (pin "8") (pinfunction "RBR5_8") (pintype "tri_state"))
      (node (ref "IC6") (pin "10") (pinfunction "3B_10") (pintype "input"))
    )
    (net (code "158") (name "/RB5") (class "Default")
      (node (ref "IC20") (pin "7") (pinfunction "RBR6_7") (pintype "tri_state"))
      (node (ref "IC6") (pin "13") (pinfunction "4B_13") (pintype "input"))
    )
    (net (code "159") (name "/RB6") (class "Default")
      (node (ref "IC20") (pin "6") (pinfunction "RBR7_6") (pintype "tri_state"))
      (node (ref "IC7") (pin "6") (pinfunction "2B_6") (pintype "input"))
    )
    (net (code "160") (name "/RB7") (class "Default")
      (node (ref "IC20") (pin "5") (pinfunction "RBR8_5") (pintype "tri_state"))
      (node (ref "IC7") (pin "3") (pinfunction "1B_3") (pintype "input"))
    )
    (net (code "161") (name "/RDATA0") (class "Default")
      (node (ref "IC20") (pin "20") (pinfunction "RRI_20") (pintype "input"))
    )
    (net (code "162") (name "/SYNC") (class "Default")
      (node (ref "IC2") (pin "16") (pinfunction "Y2_16") (pintype "tri_state"))
      (node (ref "IC2") (pin "17") (pinfunction "A4_17") (pintype "input"))
    )
    (net (code "163") (name "/TSB") (class "Default")
      (node (ref "IC20") (pin "36") (pinfunction "SBS_36") (pintype "input"))
      (node (ref "TSB") (pin "2") (pinfunction "2_2") (pintype "passive"))
    )
    (net (code "164") (name "/XDATA0") (class "Default")
      (node (ref "IC20") (pin "25") (pinfunction "TRO_25") (pintype "output"))
    )
    (net (code "165") (name "/XRDY0") (class "Default")
      (node (ref "IC20") (pin "22") (pinfunction "TBRE_22") (pintype "tri_state"))
      (node (ref "IC8") (pin "13") (pinfunction "4B_13") (pintype "input"))
    )
    (net (code "166") (name "/~{BBS7}") (class "Default")
      (node (ref "EDGE$") (pin "AP2") (pinfunction "1_AP2") (pintype "bidirectional"))
      (node (ref "IC2") (pin "11") (pinfunction "A1_11") (pintype "input"))
    )
    (net (code "167") (name "/~{BDAL0}") (class "Default")
      (node (ref "EDGE$") (pin "AU2") (pinfunction "1_AU2") (pintype "bidirectional"))
      (node (ref "IC3") (pin "11") (pinfunction "A1_11") (pintype "input"))
      (node (ref "IC4") (pin "9") (pinfunction "Y1_9") (pintype "tri_state"))
    )
    (net (code "168") (name "/~{BDAL1}") (class "Default")
      (node (ref "EDGE$") (pin "AV2") (pinfunction "1_AV2") (pintype "bidirectional"))
      (node (ref "IC3") (pin "13") (pinfunction "A2_13") (pintype "input"))
      (node (ref "IC4") (pin "7") (pinfunction "Y2_7") (pintype "tri_state"))
    )
    (net (code "169") (name "/~{BDAL2}") (class "Default")
      (node (ref "EDGE$") (pin "BE2") (pinfunction "1_BE2") (pintype "bidirectional"))
      (node (ref "IC3") (pin "8") (pinfunction "A4_8") (pintype "input"))
      (node (ref "IC4") (pin "12") (pinfunction "Y4_12") (pintype "tri_state"))
    )
    (net (code "170") (name "/~{BDAL3}") (class "Default")
      (node (ref "EDGE$") (pin "BF2") (pinfunction "1_BF2") (pintype "bidirectional"))
      (node (ref "IC3") (pin "6") (pinfunction "A3_6") (pintype "input"))
      (node (ref "IC4") (pin "14") (pinfunction "Y3_14") (pintype "tri_state"))
    )
    (net (code "171") (name "/~{BDAL4}") (class "Default")
      (node (ref "EDGE$") (pin "BH2") (pinfunction "1_BH2") (pintype "bidirectional"))
      (node (ref "IC3") (pin "4") (pinfunction "A2_4") (pintype "input"))
      (node (ref "IC4") (pin "16") (pinfunction "Y2_16") (pintype "tri_state"))
    )
    (net (code "172") (name "/~{BDAL5}") (class "Default")
      (node (ref "EDGE$") (pin "BJ2") (pinfunction "1_BJ2") (pintype "bidirectional"))
      (node (ref "IC3") (pin "2") (pinfunction "A1_2") (pintype "input"))
      (node (ref "IC4") (pin "18") (pinfunction "Y1_18") (pintype "tri_state"))
    )
    (net (code "173") (name "/~{BDAL6}") (class "Default")
      (node (ref "EDGE$") (pin "BK2") (pinfunction "1_BK2") (pintype "bidirectional"))
      (node (ref "IC3") (pin "15") (pinfunction "A3_15") (pintype "input"))
      (node (ref "IC4") (pin "5") (pinfunction "Y3_5") (pintype "tri_state"))
    )
    (net (code "174") (name "/~{BDAL7}") (class "Default")
      (node (ref "EDGE$") (pin "BL2") (pinfunction "1_BL2") (pintype "bidirectional"))
      (node (ref "IC3") (pin "17") (pinfunction "A4_17") (pintype "input"))
      (node (ref "IC4") (pin "3") (pinfunction "Y4_3") (pintype "tri_state"))
    )
    (net (code "175") (name "/~{BDAL8}") (class "Default")
      (node (ref "EDGE$") (pin "BM2") (pinfunction "1_BM2") (pintype "bidirectional"))
      (node (ref "IC1") (pin "11") (pinfunction "A1_11") (pintype "input"))
    )
    (net (code "176") (name "/~{BDAL9}") (class "Default")
      (node (ref "EDGE$") (pin "BN2") (pinfunction "1_BN2") (pintype "bidirectional"))
      (node (ref "IC1") (pin "8") (pinfunction "A4_8") (pintype "input"))
    )
    (net (code "177") (name "/~{BDAL10}") (class "Default")
      (node (ref "EDGE$") (pin "BP2") (pinfunction "1_BP2") (pintype "bidirectional"))
      (node (ref "IC1") (pin "6") (pinfunction "A3_6") (pintype "input"))
    )
    (net (code "178") (name "/~{BDAL11}") (class "Default")
      (node (ref "EDGE$") (pin "BR2") (pinfunction "1_BR2") (pintype "bidirectional"))
      (node (ref "IC1") (pin "4") (pinfunction "A2_4") (pintype "input"))
    )
    (net (code "179") (name "/~{BDAL12}") (class "Default")
      (node (ref "EDGE$") (pin "BS2") (pinfunction "1_BS2") (pintype "bidirectional"))
      (node (ref "IC1") (pin "2") (pinfunction "A1_2") (pintype "input"))
    )
    (net (code "180") (name "/~{BDAL13}") (class "Default")
      (node (ref "EDGE$") (pin "BT2") (pinfunction "1_BT2") (pintype "bidirectional"))
    )
    (net (code "181") (name "/~{BDAL14}") (class "Default")
      (node (ref "EDGE$") (pin "BU2") (pinfunction "1_BU2") (pintype "bidirectional"))
    )
    (net (code "182") (name "/~{BDAL15}") (class "Default")
      (node (ref "EDGE$") (pin "BV2") (pinfunction "1_BV2") (pintype "bidirectional"))
    )
    (net (code "183") (name "/~{BDIN}") (class "Default")
      (node (ref "EDGE$") (pin "AH2") (pinfunction "1_AH2") (pintype "bidirectional"))
      (node (ref "IC2") (pin "8") (pinfunction "A4_8") (pintype "input"))
    )
    (net (code "184") (name "/~{BDOUT}") (class "Default")
      (node (ref "EDGE$") (pin "AE2") (pinfunction "1_AE2") (pintype "bidirectional"))
      (node (ref "IC2") (pin "13") (pinfunction "A2_13") (pintype "input"))
    )
    (net (code "185") (name "/~{BHALT}") (class "Default")
      (node (ref "EDGE$") (pin "AP1") (pinfunction "1_AP1") (pintype "bidirectional"))
      (node (ref "H1") (pin "1") (pinfunction "1_1") (pintype "passive"))
    )
    (net (code "186") (name "/~{BIAKI}") (class "Default")
      (node (ref "EDGE$") (pin "AM2") (pinfunction "1_AM2") (pintype "bidirectional"))
      (node (ref "IC2") (pin "2") (pinfunction "A1_2") (pintype "input"))
    )
    (net (code "187") (name "/~{BIAKO}") (class "Default")
      (node (ref "EDGE$") (pin "AN2") (pinfunction "1_AN2") (pintype "bidirectional"))
    )
    (net (code "188") (name "/~{BINIT}") (class "Default")
      (node (ref "EDGE$") (pin "AT2") (pinfunction "1_AT2") (pintype "bidirectional"))
      (node (ref "IC2") (pin "15") (pinfunction "A3_15") (pintype "input"))
    )
    (net (code "189") (name "/~{BIRQ4}") (class "Default")
      (node (ref "EDGE$") (pin "AL2") (pinfunction "1_AL2") (pintype "bidirectional"))
    )
    (net (code "190") (name "/~{BRPLY}") (class "Default")
      (node (ref "EDGE$") (pin "AF2") (pinfunction "1_AF2") (pintype "bidirectional"))
    )
    (net (code "191") (name "/~{BSYNC}") (class "Default")
      (node (ref "EDGE$") (pin "AJ2") (pinfunction "1_AJ2") (pintype "bidirectional"))
      (node (ref "IC2") (pin "4") (pinfunction "A2_4") (pintype "input"))
    )
    (net (code "192") (name "/~{DR_R0}") (class "Default")
      (node (ref "IC18") (pin "6") (pinfunction "O_6") (pintype "output"))
      (node (ref "IC20") (pin "18") (pinfunction "~{DRR}_18") (pintype "input"))
    )
    (net (code "193") (name "/~{INIT}") (class "Default")
      (node (ref "IC2") (pin "14") (pinfunction "Y3_14") (pintype "tri_state"))
    )
    (net (code "194") (name "/~{RRBF0}") (class "Default")
      (node (ref "IC20") (pin "4") (pinfunction "RRD_4") (pintype "input"))
    )
    (net (code "195") (name "/~{SYNC}") (class "Default")
      (node (ref "IC2") (pin "3") (pinfunction "Y4_3") (pintype "tri_state"))
    )
    (net (code "196") (name "/~{WXBF0}") (class "Default")
      (node (ref "IC20") (pin "23") (pinfunction "~{TBRL}_23") (pintype "input"))
    )
    (net (code "197") (name "GND") (class "Default")
      (node (ref "A10") (pin "1") (pinfunction "1_1") (pintype "passive"))
      (node (ref "A11") (pin "1") (pinfunction "1_1") (pintype "passive"))
      (node (ref "A12") (pin "1") (pinfunction "1_1") (pintype "passive"))
      (node (ref "A3") (pin "1") (pinfunction "1_1") (pintype "passive"))
      (node (ref "A4") (pin "1") (pinfunction "1_1") (pintype "passive"))
      (node (ref "A5") (pin "1") (pinfunction "1_1") (pintype "passive"))
      (node (ref "A6") (pin "1") (pinfunction "1_1") (pintype "passive"))
      (node (ref "A7") (pin "1") (pinfunction "1_1") (pintype "passive"))
      (node (ref "A8") (pin "1") (pinfunction "1_1") (pintype "passive"))
      (node (ref "A9") (pin "1") (pinfunction "1_1") (pintype "passive"))
      (node (ref "EDGE$") (pin "AJ1") (pinfunction "1_AJ1") (pintype "bidirectional"))
      (node (ref "EDGE$") (pin "AM1") (pinfunction "1_AM1") (pintype "bidirectional"))
      (node (ref "EDGE$") (pin "BC2") (pinfunction "1_BC2") (pintype "bidirectional"))
      (node (ref "EDGE$") (pin "BM1") (pinfunction "1_BM1") (pintype "bidirectional"))
      (node (ref "EDGE$") (pin "BT1") (pinfunction "1_BT1") (pintype "bidirectional"))
      (node (ref "EPS") (pin "1") (pinfunction "1_1") (pintype "passive"))
      (node (ref "IC1") (pin "1") (pinfunction "G_1") (pintype "input"))
      (node (ref "IC1") (pin "19") (pinfunction "G_19") (pintype "input"))
      (node (ref "IC12") (pin "1") (pinfunction "I0_1") (pintype "input"))
      (node (ref "IC12") (pin "2") (pinfunction "I1_2") (pintype "input"))
      (node (ref "IC2") (pin "1") (pinfunction "G_1") (pintype "input"))
      (node (ref "IC2") (pin "19") (pinfunction "G_19") (pintype "input"))
      (node (ref "IC20") (pin "16") (pinfunction "SFD_16") (pintype "input"))
      (node (ref "IC24") (pin "12") (pinfunction "RC_12") (pintype "input"))
      (node (ref "IC24") (pin "13") (pinfunction "I_13") (pintype "input"))
      (node (ref "IC24") (pin "7") (pinfunction "GND_7") (pintype "power_in"))
      (node (ref "IC25") (pin "10") (pinfunction "I1_10") (pintype "input"))
      (node (ref "IC25") (pin "11") (pinfunction "I3_11") (pintype "input"))
      (node (ref "IC25") (pin "3") (pinfunction "I2_3") (pintype "input"))
      (node (ref "IC25") (pin "4") (pinfunction "I0_4") (pintype "input"))
      (node (ref "IC28") (pin "4") (pinfunction "EMI_4") (pintype "passive"))
      (node (ref "IC3") (pin "1") (pinfunction "G_1") (pintype "input"))
      (node (ref "IC3") (pin "19") (pinfunction "G_19") (pintype "input"))
      (node (ref "IC5") (pin "11") (pinfunction "~{STB}_11") (pintype "input"))
      (node (ref "NB1") (pin "1") (pinfunction "1_1") (pintype "passive"))
      (node (ref "NB2") (pin "1") (pinfunction "1_1") (pintype "passive"))
      (node (ref "NP") (pin "1") (pinfunction "1_1") (pintype "passive"))
      (node (ref "Q1") (pin "1") (pinfunction "E_1") (pintype "passive"))
      (node (ref "TSB") (pin "1") (pinfunction "1_1") (pintype "passive"))
      (node (ref "V3") (pin "1") (pinfunction "1_1") (pintype "passive"))
      (node (ref "V4") (pin "1") (pinfunction "1_1") (pintype "passive"))
      (node (ref "V5") (pin "1") (pinfunction "1_1") (pintype "passive"))
      (node (ref "V6") (pin "1") (pinfunction "1_1") (pintype "passive"))
      (node (ref "V7") (pin "1") (pinfunction "1_1") (pintype "passive"))
    )
    (net (code "198") (name "Net-(IC6A-2A)") (class "Default")
      (node (ref "IC6") (pin "5") (pinfunction "2A_5") (pintype "input"))
      (node (ref "R16") (pin "2") (pinfunction "2_2") (pintype "passive"))
      (node (ref "V3") (pin "2") (pinfunction "2_2") (pintype "passive"))
    )
    (net (code "199") (name "Net-(IC6A-3A)") (class "Default")
      (node (ref "IC6") (pin "11") (pinfunction "3A_11") (pintype "input"))
      (node (ref "R17") (pin "2") (pinfunction "2_2") (pintype "passive"))
      (node (ref "V4") (pin "2") (pinfunction "2_2") (pintype "passive"))
    )
    (net (code "200") (name "Net-(IC6A-4A)") (class "Default")
      (node (ref "IC6") (pin "14") (pinfunction "4A_14") (pintype "input"))
      (node (ref "R18") (pin "2") (pinfunction "2_2") (pintype "passive"))
      (node (ref "V5") (pin "2") (pinfunction "2_2") (pintype "passive"))
    )
    (net (code "201") (name "Net-(IC6A-G)") (class "Default")
      (node (ref "IC6") (pin "15") (pinfunction "G_15") (pintype "input"))
      (node (ref "IC7") (pin "15") (pinfunction "G_15") (pintype "input"))
    )
    (net (code "202") (name "Net-(IC6A-~{A}{slash}B)") (class "Default")
      (node (ref "IC6") (pin "1") (pinfunction "~{A}/B_1") (pintype "input"))
      (node (ref "IC7") (pin "1") (pinfunction "~{A}/B_1") (pintype "input"))
    )
    (net (code "203") (name "Net-(IC7A-1A)") (class "Default")
      (node (ref "IC7") (pin "2") (pinfunction "1A_2") (pintype "input"))
      (node (ref "R15") (pin "2") (pinfunction "2_2") (pintype "passive"))
      (node (ref "V7") (pin "2") (pinfunction "2_2") (pintype "passive"))
    )
    (net (code "204") (name "Net-(IC7A-1Y)") (class "Default")
      (node (ref "IC7") (pin "4") (pinfunction "1Y_4") (pintype "tri_state"))
      (node (ref "IC8") (pin "12") (pinfunction "4Y_12") (pintype "tri_state"))
    )
    (net (code "205") (name "Net-(IC7A-2A)") (class "Default")
      (node (ref "IC7") (pin "5") (pinfunction "2A_5") (pintype "input"))
      (node (ref "R14") (pin "2") (pinfunction "2_2") (pintype "passive"))
      (node (ref "V6") (pin "2") (pinfunction "2_2") (pintype "passive"))
    )
    (net (code "206") (name "Net-(IC7A-2Y)") (class "Default")
      (node (ref "IC7") (pin "7") (pinfunction "2Y_7") (pintype "tri_state"))
      (node (ref "IC8") (pin "9") (pinfunction "3Y_9") (pintype "tri_state"))
    )
    (net (code "207") (name "Net-(IC7A-3Y)") (class "Default")
      (node (ref "IC7") (pin "9") (pinfunction "3Y_9") (pintype "tri_state"))
      (node (ref "IC8") (pin "7") (pinfunction "2Y_7") (pintype "tri_state"))
    )
    (net (code "208") (name "Net-(IC7A-4Y)") (class "Default")
      (node (ref "IC7") (pin "12") (pinfunction "4Y_12") (pintype "tri_state"))
      (node (ref "IC8") (pin "4") (pinfunction "1Y_4") (pintype "tri_state"))
    )
    (net (code "209") (name "Net-(IC9C-I0)") (class "Default")
      (node (ref "IC9") (pin "10") (pinfunction "I1_10") (pintype "input"))
      (node (ref "IC9") (pin "9") (pinfunction "I0_9") (pintype "input"))
    )
    (net (code "210") (name "Net-(IC10A-I1)") (class "Default")
      (node (ref "IC10") (pin "13") (pinfunction "I1_13") (pintype "input"))
      (node (ref "IC10") (pin "2") (pinfunction "I1_2") (pintype "input"))
    )
    (net (code "211") (name "Net-(IC13A-D)") (class "Default")
      (node (ref "IC13") (pin "12") (pinfunction "D_12") (pintype "input"))
      (node (ref "IC13") (pin "2") (pinfunction "D_2") (pintype "input"))
    )
    (net (code "212") (name "Net-(IC15A-D)") (class "Default")
      (node (ref "IC15") (pin "12") (pinfunction "D_12") (pintype "input"))
      (node (ref "IC15") (pin "2") (pinfunction "D_2") (pintype "input"))
    )
    (net (code "213") (name "Net-(IC16B-I1)") (class "Default")
      (node (ref "IC16") (pin "5") (pinfunction "I1_5") (pintype "input"))
      (node (ref "IC17") (pin "12") (pinfunction "D_12") (pintype "input"))
    )
    (net (code "214") (name "Net-(IC17A-CLK)") (class "Default")
      (node (ref "IC17") (pin "11") (pinfunction "CLK_11") (pintype "input"))
      (node (ref "IC17") (pin "3") (pinfunction "CLK_3") (pintype "input"))
    )
    (net (code "215") (name "Net-(IC17A-PRE)") (class "Default")
      (node (ref "IC17") (pin "10") (pinfunction "PRE_10") (pintype "input"))
      (node (ref "IC17") (pin "4") (pinfunction "PRE_4") (pintype "input"))
    )
    (net (code "216") (name "Net-(IC25A-Q0)") (class "Default")
      (node (ref "IC25") (pin "5") (pinfunction "Q0_5") (pintype "output"))
      (node (ref "IC25") (pin "6") (pinfunction "/5_6") (pintype "bidirectional"))
    )
    (net (code "217") (name "Net-(Q1-C)") (class "Default")
      (node (ref "H1") (pin "2") (pinfunction "2_2") (pintype "passive"))
      (node (ref "Q1") (pin "3") (pinfunction "C_3") (pintype "passive"))
    )
    (net (code "218") (name "Net-(R34-Pad2)") (class "Default")
      (node (ref "R34") (pin "2") (pinfunction "2_2") (pintype "passive"))
      (node (ref "R35") (pin "2") (pinfunction "2_2") (pintype "passive"))
    )
    (net (code "219") (name "VCC") (class "Default")
      (node (ref "EDGE$") (pin "AA2") (pinfunction "1_AA2") (pintype "bidirectional"))
      (node (ref "EDGE$") (pin "BV1") (pinfunction "1_BV1") (pintype "bidirectional"))
      (node (ref "IC16") (pin "13") (pinfunction "I1_13") (pintype "input"))
      (node (ref "IC16") (pin "2") (pinfunction "I1_2") (pintype "input"))
      (node (ref "IC20") (pin "34") (pinfunction "CRL_34") (pintype "input"))
      (node (ref "IC24") (pin "9") (pinfunction "RC_9") (pintype "input"))
      (node (ref "IC25") (pin "1") (pinfunction "~{LD}_1") (pintype "input"))
      (node (ref "R14") (pin "1") (pinfunction "1_1") (pintype "passive"))
      (node (ref "R15") (pin "1") (pinfunction "1_1") (pintype "passive"))
      (node (ref "R16") (pin "1") (pinfunction "1_1") (pintype "passive"))
      (node (ref "R17") (pin "1") (pinfunction "1_1") (pintype "passive"))
      (node (ref "R18") (pin "1") (pinfunction "1_1") (pintype "passive"))
      (node (ref "R19") (pin "1") (pinfunction "1_1") (pintype "passive"))
      (node (ref "R21") (pin "1") (pinfunction "1_1") (pintype "passive"))
      (node (ref "R23") (pin "1") (pinfunction "1_1") (pintype "passive"))
      (node (ref "R25") (pin "1") (pinfunction "1_1") (pintype "passive"))
      (node (ref "R26") (pin "1") (pinfunction "1_1") (pintype "passive"))
      (node (ref "R27") (pin "1") (pinfunction "1_1") (pintype "passive"))
      (node (ref "R28") (pin "1") (pinfunction "1_1") (pintype "passive"))
      (node (ref "R29") (pin "1") (pinfunction "1_1") (pintype "passive"))
      (node (ref "R31") (pin "1") (pinfunction "1_1") (pintype "passive"))
      (node (ref "R32") (pin "1") (pinfunction "1_1") (pintype "passive"))
    )
    (net (code "220") (name "unconnected-(IC1B-A3-Pad15)") (class "Default")
      (node (ref "IC1") (pin "15") (pinfunction "A3_15") (pintype "input"))
    )
    (net (code "221") (name "unconnected-(IC1B-A4-Pad17)") (class "Default")
      (node (ref "IC1") (pin "17") (pinfunction "A4_17") (pintype "input"))
    )
    (net (code "222") (name "unconnected-(IC1B-Y3-Pad5)") (class "Default")
      (node (ref "IC1") (pin "5") (pinfunction "Y3_5") (pintype "tri_state"))
    )
    (net (code "223") (name "unconnected-(IC1B-Y4-Pad3)") (class "Default")
      (node (ref "IC1") (pin "3") (pinfunction "Y4_3") (pintype "tri_state"))
    )
    (net (code "224") (name "unconnected-(IC6A-4Y-Pad12)") (class "Default")
      (node (ref "IC6") (pin "12") (pinfunction "4Y_12") (pintype "output"))
    )
    (net (code "225") (name "unconnected-(IC8A-1B-Pad3)") (class "Default")
      (node (ref "IC8") (pin "3") (pinfunction "1B_3") (pintype "input"))
    )
    (net (code "226") (name "unconnected-(IC8A-3A-Pad11)") (class "Default")
      (node (ref "IC8") (pin "11") (pinfunction "3A_11") (pintype "input"))
    )
    (net (code "227") (name "unconnected-(IC9D-I0-Pad12)") (class "Default")
      (node (ref "IC9") (pin "12") (pinfunction "I0_12") (pintype "input"))
    )
    (net (code "228") (name "unconnected-(IC9D-I1-Pad13)") (class "Default")
      (node (ref "IC9") (pin "13") (pinfunction "I1_13") (pintype "input"))
    )
    (net (code "229") (name "unconnected-(IC10B-O-Pad6)") (class "Default")
      (node (ref "IC10") (pin "6") (pinfunction "O_6") (pintype "output"))
    )
    (net (code "230") (name "unconnected-(IC10C-I0-Pad9)") (class "Default")
      (node (ref "IC10") (pin "9") (pinfunction "I0_9") (pintype "input"))
    )
    (net (code "231") (name "unconnected-(IC10C-O-Pad8)") (class "Default")
      (node (ref "IC10") (pin "8") (pinfunction "O_8") (pintype "output"))
    )
    (net (code "232") (name "unconnected-(IC11B-I0-Pad4)") (class "Default")
      (node (ref "IC11") (pin "4") (pinfunction "I0_4") (pintype "input"))
    )
    (net (code "233") (name "unconnected-(IC11B-I1-Pad5)") (class "Default")
      (node (ref "IC11") (pin "5") (pinfunction "I1_5") (pintype "input"))
    )
    (net (code "234") (name "unconnected-(IC11C-O-Pad8)") (class "Default")
      (node (ref "IC11") (pin "8") (pinfunction "O_8") (pintype "output"))
    )
    (net (code "235") (name "unconnected-(IC11D-I0-Pad12)") (class "Default")
      (node (ref "IC11") (pin "12") (pinfunction "I0_12") (pintype "input"))
    )
    (net (code "236") (name "unconnected-(IC12A-I2-Pad13)") (class "Default")
      (node (ref "IC12") (pin "13") (pinfunction "I2_13") (pintype "input"))
    )
    (net (code "237") (name "unconnected-(IC12B-I1-Pad4)") (class "Default")
      (node (ref "IC12") (pin "4") (pinfunction "I1_4") (pintype "input"))
    )
    (net (code "238") (name "unconnected-(IC12C-I1-Pad10)") (class "Default")
      (node (ref "IC12") (pin "10") (pinfunction "I1_10") (pintype "input"))
    )
    (net (code "239") (name "unconnected-(IC12C-O-Pad8)") (class "Default")
      (node (ref "IC12") (pin "8") (pinfunction "O_8") (pintype "output"))
    )
    (net (code "240") (name "unconnected-(IC13A-CLK-Pad3)") (class "Default")
      (node (ref "IC13") (pin "3") (pinfunction "CLK_3") (pintype "input"))
    )
    (net (code "241") (name "unconnected-(IC13A-PRE-Pad4)") (class "Default")
      (node (ref "IC13") (pin "4") (pinfunction "PRE_4") (pintype "input"))
    )
    (net (code "242") (name "unconnected-(IC13A-~{Q}-Pad6)") (class "Default")
      (node (ref "IC13") (pin "6") (pinfunction "~{Q}_6") (pintype "output"))
    )
    (net (code "243") (name "unconnected-(IC13B-PRE-Pad10)") (class "Default")
      (node (ref "IC13") (pin "10") (pinfunction "PRE_10") (pintype "input"))
    )
    (net (code "244") (name "unconnected-(IC13B-Q-Pad9)") (class "Default")
      (node (ref "IC13") (pin "9") (pinfunction "Q_9") (pintype "output"))
    )
    (net (code "245") (name "unconnected-(IC13B-~{Q}-Pad8)") (class "Default")
      (node (ref "IC13") (pin "8") (pinfunction "~{Q}_8") (pintype "output"))
    )
    (net (code "246") (name "unconnected-(IC14B-I1-Pad4)") (class "Default")
      (node (ref "IC14") (pin "4") (pinfunction "I1_4") (pintype "input"))
    )
    (net (code "247") (name "unconnected-(IC14C-O-Pad8)") (class "Default")
      (node (ref "IC14") (pin "8") (pinfunction "O_8") (pintype "output"))
    )
    (net (code "248") (name "unconnected-(IC15A-CLR-Pad1)") (class "Default")
      (node (ref "IC15") (pin "1") (pinfunction "CLR_1") (pintype "input"))
    )
    (net (code "249") (name "unconnected-(IC15A-~{Q}-Pad6)") (class "Default")
      (node (ref "IC15") (pin "6") (pinfunction "~{Q}_6") (pintype "output"))
    )
    (net (code "250") (name "unconnected-(IC15B-PRE-Pad10)") (class "Default")
      (node (ref "IC15") (pin "10") (pinfunction "PRE_10") (pintype "input"))
    )
    (net (code "251") (name "unconnected-(IC15B-~{Q}-Pad8)") (class "Default")
      (node (ref "IC15") (pin "8") (pinfunction "~{Q}_8") (pintype "output"))
    )
    (net (code "252") (name "unconnected-(IC16B-O-Pad6)") (class "Default")
      (node (ref "IC16") (pin "6") (pinfunction "O_6") (pintype "output"))
    )
    (net (code "253") (name "unconnected-(IC16C-O-Pad8)") (class "Default")
      (node (ref "IC16") (pin "8") (pinfunction "O_8") (pintype "output"))
    )
    (net (code "254") (name "unconnected-(IC17A-CLR-Pad1)") (class "Default")
      (node (ref "IC17") (pin "1") (pinfunction "CLR_1") (pintype "input"))
    )
    (net (code "255") (name "unconnected-(IC17A-Q-Pad5)") (class "Default")
      (node (ref "IC17") (pin "5") (pinfunction "Q_5") (pintype "output"))
    )
    (net (code "256") (name "unconnected-(IC17B-CLR-Pad13)") (class "Default")
      (node (ref "IC17") (pin "13") (pinfunction "CLR_13") (pintype "input"))
    )
    (net (code "257") (name "unconnected-(IC18A-O-Pad12)") (class "Default")
      (node (ref "IC18") (pin "12") (pinfunction "O_12") (pintype "output"))
    )
    (net (code "258") (name "unconnected-(IC19A-D2-Pad3)") (class "Default")
      (node (ref "IC19") (pin "3") (pinfunction "D2_3") (pintype "input"))
    )
    (net (code "259") (name "unconnected-(IC19A-Q1-Pad16)") (class "Default")
      (node (ref "IC19") (pin "16") (pinfunction "Q1_16") (pintype "output"))
    )
    (net (code "260") (name "unconnected-(IC19A-Q2-Pad15)") (class "Default")
      (node (ref "IC19") (pin "15") (pinfunction "Q2_15") (pintype "output"))
    )
    (net (code "261") (name "unconnected-(IC19A-~{Q1}-Pad1)") (class "Default")
      (node (ref "IC19") (pin "1") (pinfunction "~{Q1}_1") (pintype "output"))
    )
    (net (code "262") (name "unconnected-(IC19A-~{Q2}-Pad14)") (class "Default")
      (node (ref "IC19") (pin "14") (pinfunction "~{Q2}_14") (pintype "output"))
    )
    (net (code "263") (name "unconnected-(IC20A-TRE-Pad24)") (class "Default")
      (node (ref "IC20") (pin "24") (pinfunction "TRE_24") (pintype "output"))
    )
    (net (code "264") (name "unconnected-(IC21A-I0-Pad2)") (class "Default")
      (node (ref "IC21") (pin "2") (pinfunction "I0_2") (pintype "input"))
    )
    (net (code "265") (name "unconnected-(IC21A-I1-Pad3)") (class "Default")
      (node (ref "IC21") (pin "3") (pinfunction "I1_3") (pintype "input"))
    )
    (net (code "266") (name "unconnected-(IC21C-O-Pad10)") (class "Default")
      (node (ref "IC21") (pin "10") (pinfunction "O_10") (pintype "output"))
    )
    (net (code "267") (name "unconnected-(IC21D-O-Pad13)") (class "Default")
      (node (ref "IC21") (pin "13") (pinfunction "O_13") (pintype "output"))
    )
    (net (code "268") (name "unconnected-(IC22A-PRE-Pad4)") (class "Default")
      (node (ref "IC22") (pin "4") (pinfunction "PRE_4") (pintype "input"))
    )
    (net (code "269") (name "unconnected-(IC22A-Q-Pad5)") (class "Default")
      (node (ref "IC22") (pin "5") (pinfunction "Q_5") (pintype "output"))
    )
    (net (code "270") (name "unconnected-(IC22A-~{Q}-Pad6)") (class "Default")
      (node (ref "IC22") (pin "6") (pinfunction "~{Q}_6") (pintype "output"))
    )
    (net (code "271") (name "unconnected-(IC22B-PRE-Pad10)") (class "Default")
      (node (ref "IC22") (pin "10") (pinfunction "PRE_10") (pintype "input"))
    )
    (net (code "272") (name "unconnected-(IC22B-~{Q}-Pad8)") (class "Default")
      (node (ref "IC22") (pin "8") (pinfunction "~{Q}_8") (pintype "output"))
    )
    (net (code "273") (name "unconnected-(IC23A-I-Pad2)") (class "Default")
      (node (ref "IC23") (pin "2") (pinfunction "I_2") (pintype "input"))
    )
    (net (code "274") (name "unconnected-(IC23B-I0-Pad4)") (class "Default")
      (node (ref "IC23") (pin "4") (pinfunction "I0_4") (pintype "input"))
    )
    (net (code "275") (name "unconnected-(IC23B-I1-Pad5)") (class "Default")
      (node (ref "IC23") (pin "5") (pinfunction "I1_5") (pintype "input"))
    )
    (net (code "276") (name "unconnected-(IC23B-O-Pad6)") (class "Default")
      (node (ref "IC23") (pin "6") (pinfunction "O_6") (pintype "output"))
    )
    (net (code "277") (name "unconnected-(IC23C-I0-Pad9)") (class "Default")
      (node (ref "IC23") (pin "9") (pinfunction "I0_9") (pintype "input"))
    )
    (net (code "278") (name "unconnected-(IC23D-I0-Pad12)") (class "Default")
      (node (ref "IC23") (pin "12") (pinfunction "I0_12") (pintype "input"))
    )
    (net (code "279") (name "unconnected-(IC24A-O-Pad3)") (class "Default")
      (node (ref "IC24") (pin "3") (pinfunction "O_3") (pintype "output"))
    )
    (net (code "280") (name "unconnected-(IC24A-RC-Pad2)") (class "Default")
      (node (ref "IC24") (pin "2") (pinfunction "RC_2") (pintype "input"))
    )
    (net (code "281") (name "unconnected-(IC24B-I-Pad4)") (class "Default")
      (node (ref "IC24") (pin "4") (pinfunction "I_4") (pintype "input"))
    )
    (net (code "282") (name "unconnected-(IC25A-Q1-Pad9)") (class "Default")
      (node (ref "IC25") (pin "9") (pinfunction "Q1_9") (pintype "output"))
    )
    (net (code "283") (name "unconnected-(IC25A-Q2-Pad2)") (class "Default")
      (node (ref "IC25") (pin "2") (pinfunction "Q2_2") (pintype "output"))
    )
    (net (code "284") (name "unconnected-(IC26B-I0-Pad4)") (class "Default")
      (node (ref "IC26") (pin "4") (pinfunction "I0_4") (pintype "input"))
    )
    (net (code "285") (name "unconnected-(IC27A-CO-Pad9)") (class "Default")
      (node (ref "IC27") (pin "9") (pinfunction "CO_9") (pintype "output"))
    )
    (net (code "286") (name "unconnected-(IC27A-IM-Pad15)") (class "Default")
      (node (ref "IC27") (pin "15") (pinfunction "IM_15") (pintype "input"))
    )
    (net (code "287") (name "unconnected-(IC27A-IX-Pad7)") (class "Default")
      (node (ref "IC27") (pin "7") (pinfunction "IX_7") (pintype "input"))
    )
    (net (code "288") (name "unconnected-(IC27A-OX-Pad6)") (class "Default")
      (node (ref "IC27") (pin "6") (pinfunction "OX_6") (pintype "output"))
    )
    (net (code "289") (name "unconnected-(IC27A-Q0-Pad1)") (class "Default")
      (node (ref "IC27") (pin "1") (pinfunction "Q0_1") (pintype "output"))
    )
    (net (code "290") (name "unconnected-(IC27A-Q2-Pad3)") (class "Default")
      (node (ref "IC27") (pin "3") (pinfunction "Q2_3") (pintype "output"))
    )
    (net (code "291") (name "unconnected-(IC27A-S0-Pad14)") (class "Default")
      (node (ref "IC27") (pin "14") (pinfunction "S0_14") (pintype "input"))
    )
    (net (code "292") (name "unconnected-(IC27A-S1-Pad13)") (class "Default")
      (node (ref "IC27") (pin "13") (pinfunction "S1_13") (pintype "input"))
    )
    (net (code "293") (name "unconnected-(IC27A-S2-Pad12)") (class "Default")
      (node (ref "IC27") (pin "12") (pinfunction "S2_12") (pintype "input"))
    )
    (net (code "294") (name "unconnected-(IC27A-S3-Pad11)") (class "Default")
      (node (ref "IC27") (pin "11") (pinfunction "S3_11") (pintype "input"))
    )
    (net (code "295") (name "unconnected-(IC27A-~{ECP}-Pad4)") (class "Default")
      (node (ref "IC27") (pin "4") (pinfunction "~{ECP}_4") (pintype "input"))
    )
    (net (code "296") (name "unconnected-(IC28-A-Pad1)") (class "Default")
      (node (ref "IC28") (pin "1") (pinfunction "A_1") (pintype "passive"))
    )
    (net (code "297") (name "unconnected-(IC28-BAS-Pad6)") (class "Default")
      (node (ref "IC28") (pin "6") (pinfunction "BAS_6") (pintype "passive"))
    )
    (net (code "298") (name "unconnected-(IC28-COL-Pad5)") (class "Default")
      (node (ref "IC28") (pin "5") (pinfunction "COL_5") (pintype "passive"))
    )
    (net (code "299") (name "unconnected-(IC29-A-Pad1)") (class "Default")
      (node (ref "IC29") (pin "1") (pinfunction "A_1") (pintype "passive"))
    )
    (net (code "300") (name "unconnected-(IC29-BAS-Pad6)") (class "Default")
      (node (ref "IC29") (pin "6") (pinfunction "BAS_6") (pintype "passive"))
    )
    (net (code "301") (name "unconnected-(IC29-COL-Pad5)") (class "Default")
      (node (ref "IC29") (pin "5") (pinfunction "COL_5") (pintype "passive"))
    )
    (net (code "302") (name "unconnected-(IC29-EMI-Pad4)") (class "Default")
      (node (ref "IC29") (pin "4") (pinfunction "EMI_4") (pintype "passive"))
    )
    (net (code "303") (name "unconnected-(R1-Pad1)") (class "Default")
      (node (ref "R1") (pin "1") (pinfunction "1_1") (pintype "passive"))
    )
    (net (code "304") (name "unconnected-(R1-Pad2)") (class "Default")
      (node (ref "R1") (pin "2") (pinfunction "2_2") (pintype "passive"))
    )
    (net (code "305") (name "unconnected-(R2-Pad1)") (class "Default")
      (node (ref "R2") (pin "1") (pinfunction "1_1") (pintype "passive"))
    )
    (net (code "306") (name "unconnected-(R2-Pad2)") (class "Default")
      (node (ref "R2") (pin "2") (pinfunction "2_2") (pintype "passive"))
    )
    (net (code "307") (name "unconnected-(R3-Pad1)") (class "Default")
      (node (ref "R3") (pin "1") (pinfunction "1_1") (pintype "passive"))
    )
    (net (code "308") (name "unconnected-(R4-Pad1)") (class "Default")
      (node (ref "R4") (pin "1") (pinfunction "1_1") (pintype "passive"))
    )
    (net (code "309") (name "unconnected-(R12-Pad1)") (class "Default")
      (node (ref "R12") (pin "1") (pinfunction "1_1") (pintype "passive"))
    )
    (net (code "310") (name "unconnected-(R12-Pad2)") (class "Default")
      (node (ref "R12") (pin "2") (pinfunction "2_2") (pintype "passive"))
    )
    (net (code "311") (name "unconnected-(R34-Pad1)") (class "Default")
      (node (ref "R34") (pin "1") (pinfunction "1_1") (pintype "passive"))
    )
    (net (code "312") (name "unconnected-(R35-Pad1)") (class "Default")
      (node (ref "R35") (pin "1") (pinfunction "1_1") (pintype "passive"))
    )
    (net (code "313") (name "unconnected-(R41-Pad1)") (class "Default")
      (node (ref "R41") (pin "1") (pinfunction "1_1") (pintype "passive"))
    )
    (net (code "314") (name "unconnected-(R41-Pad2)") (class "Default")
      (node (ref "R41") (pin "2") (pinfunction "2_2") (pintype "passive"))
    )
    (net (code "315") (name "unconnected-(SV1-Pad1)") (class "Default")
      (node (ref "SV1") (pin "1") (pinfunction "1_1") (pintype "passive"))
    )
    (net (code "316") (name "unconnected-(SV1-Pad2)") (class "Default")
      (node (ref "SV1") (pin "2") (pinfunction "2_2") (pintype "passive"))
    )
    (net (code "317") (name "unconnected-(SV1-Pad3)") (class "Default")
      (node (ref "SV1") (pin "3") (pinfunction "3_3") (pintype "passive"))
    )
    (net (code "318") (name "unconnected-(SV1-Pad4)") (class "Default")
      (node (ref "SV1") (pin "4") (pinfunction "4_4") (pintype "passive"))
    )
    (net (code "319") (name "unconnected-(SV1-Pad5)") (class "Default")
      (node (ref "SV1") (pin "5") (pinfunction "5_5") (pintype "passive"))
    )
    (net (code "320") (name "unconnected-(SV1-Pad6)") (class "Default")
      (node (ref "SV1") (pin "6") (pinfunction "6_6") (pintype "passive"))
    )
    (net (code "321") (name "unconnected-(SV1-Pad7)") (class "Default")
      (node (ref "SV1") (pin "7") (pinfunction "7_7") (pintype "passive"))
    )
    (net (code "322") (name "unconnected-(SV1-Pad9)") (class "Default")
      (node (ref "SV1") (pin "9") (pinfunction "9_9") (pintype "passive"))
    )
    (net (code "323") (name "unconnected-(SV1-Pad14)") (class "Default")
      (node (ref "SV1") (pin "14") (pinfunction "14_14") (pintype "passive"))
    )
    (net (code "324") (name "unconnected-(SV1-Pad15)") (class "Default")
      (node (ref "SV1") (pin "15") (pinfunction "15_15") (pintype "passive"))
    )
    (net (code "325") (name "unconnected-(SV1-Pad18)") (class "Default")
      (node (ref "SV1") (pin "18") (pinfunction "18_18") (pintype "passive"))
    )
    (net (code "326") (name "unconnected-(SV1-Pad19)") (class "Default")
      (node (ref "SV1") (pin "19") (pinfunction "19_19") (pintype "passive"))
    )
    (net (code "327") (name "unconnected-(SV1-Pad20)") (class "Default")
      (node (ref "SV1") (pin "20") (pinfunction "20_20") (pintype "passive"))
    )
    (net (code "328") (name "unconnected-(SV2-Pad2)") (class "Default")
      (node (ref "SV2") (pin "2") (pinfunction "2_2") (pintype "passive"))
    )
    (net (code "329") (name "unconnected-(SV2-Pad4)") (class "Default")
      (node (ref "SV2") (pin "4") (pinfunction "4_4") (pintype "passive"))
    )
    (net (code "330") (name "unconnected-(SV2-Pad5)") (class "Default")
      (node (ref "SV2") (pin "5") (pinfunction "5_5") (pintype "passive"))
    )
  )
)
